# X15-Pi-Shield.net
KiCad netlist of a schematic drawn in EAGLE
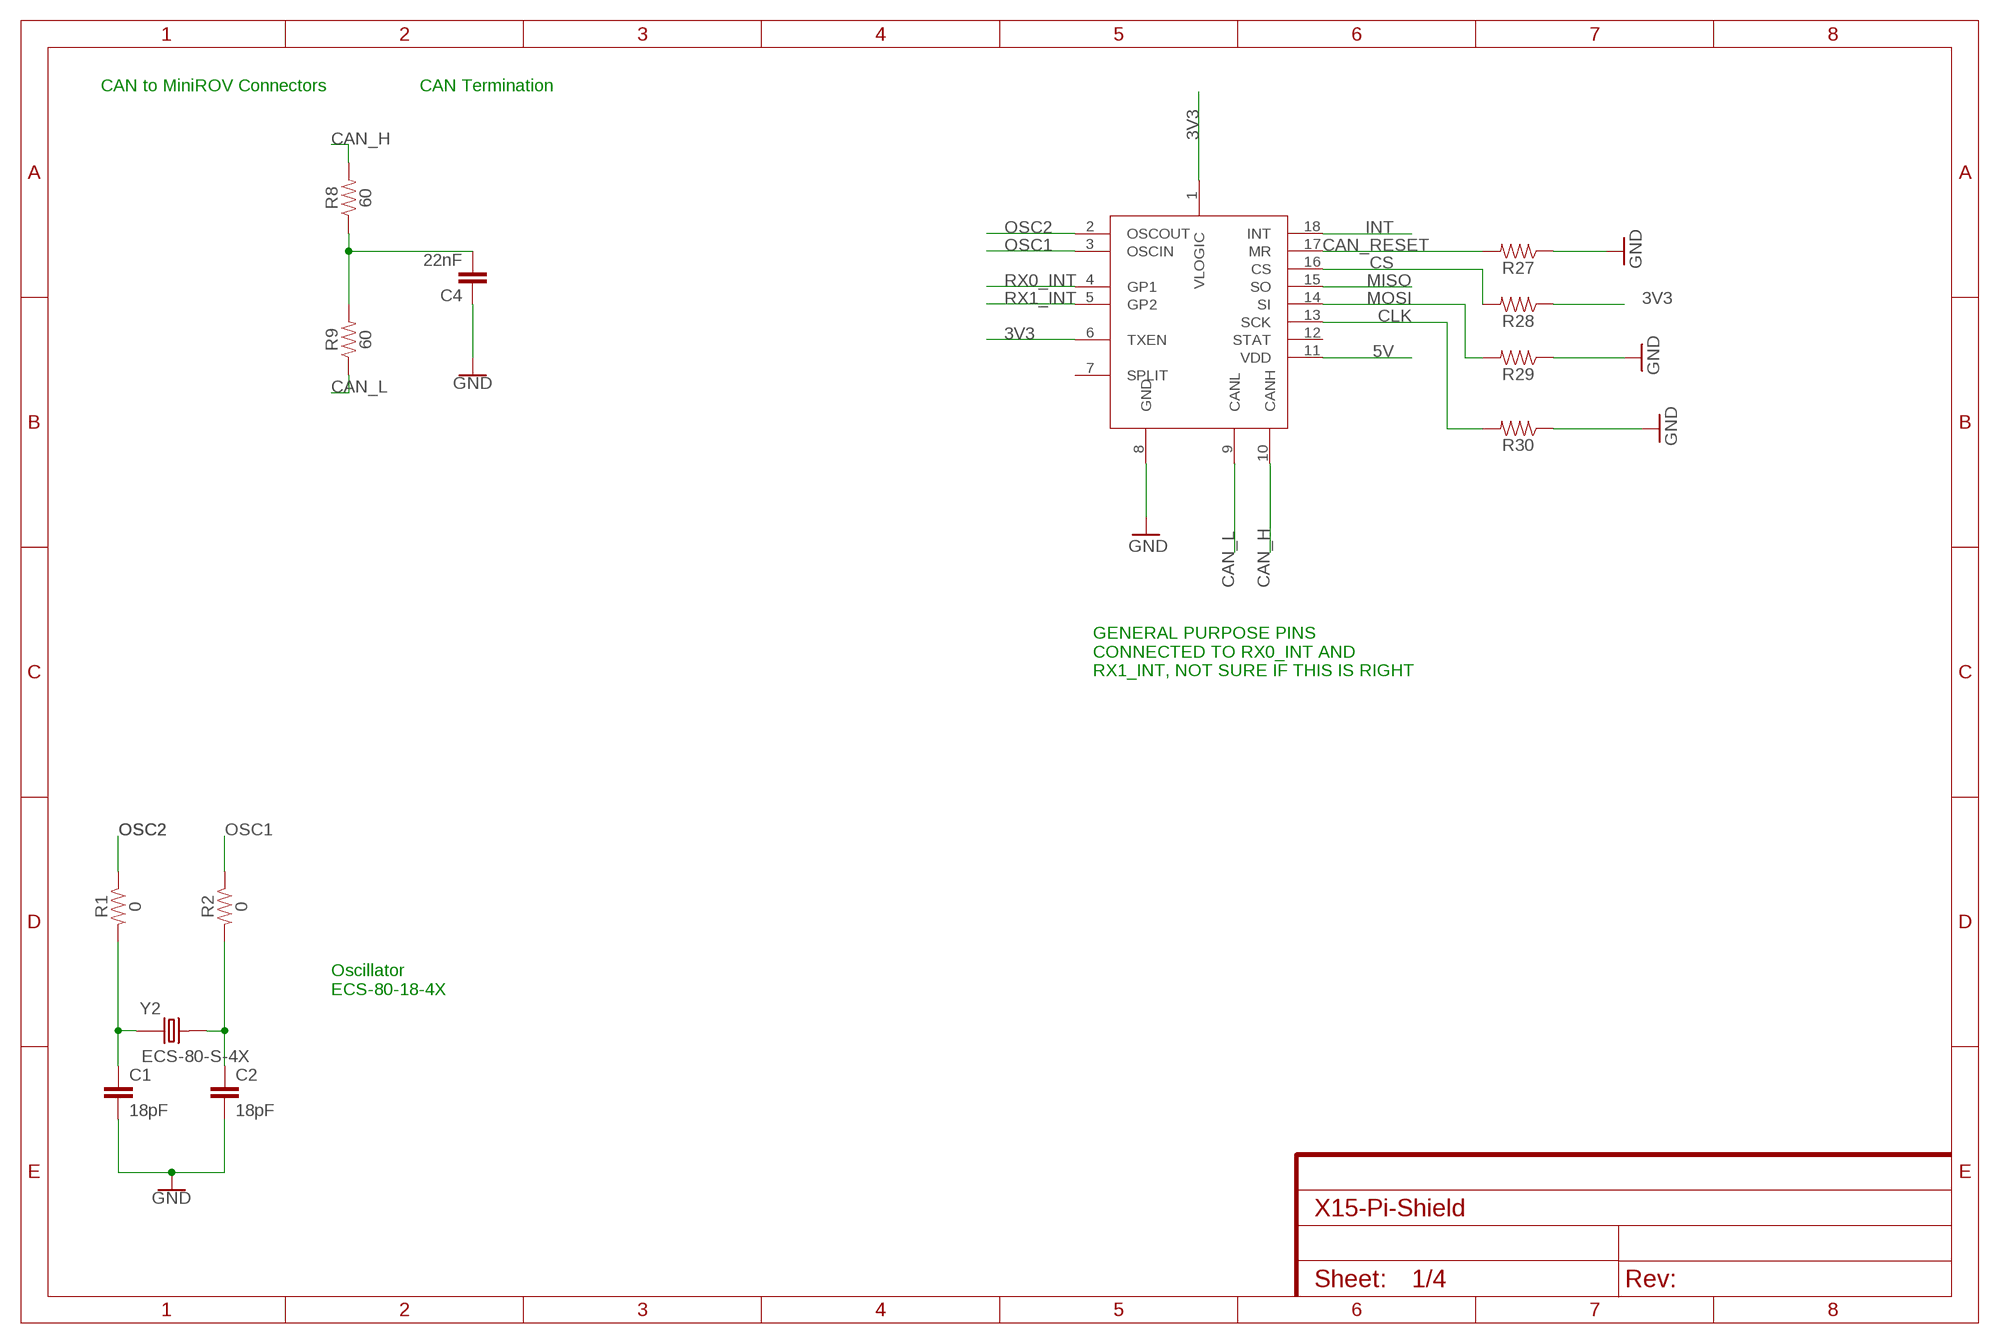
[diagram p0: schematic, sheet 1]
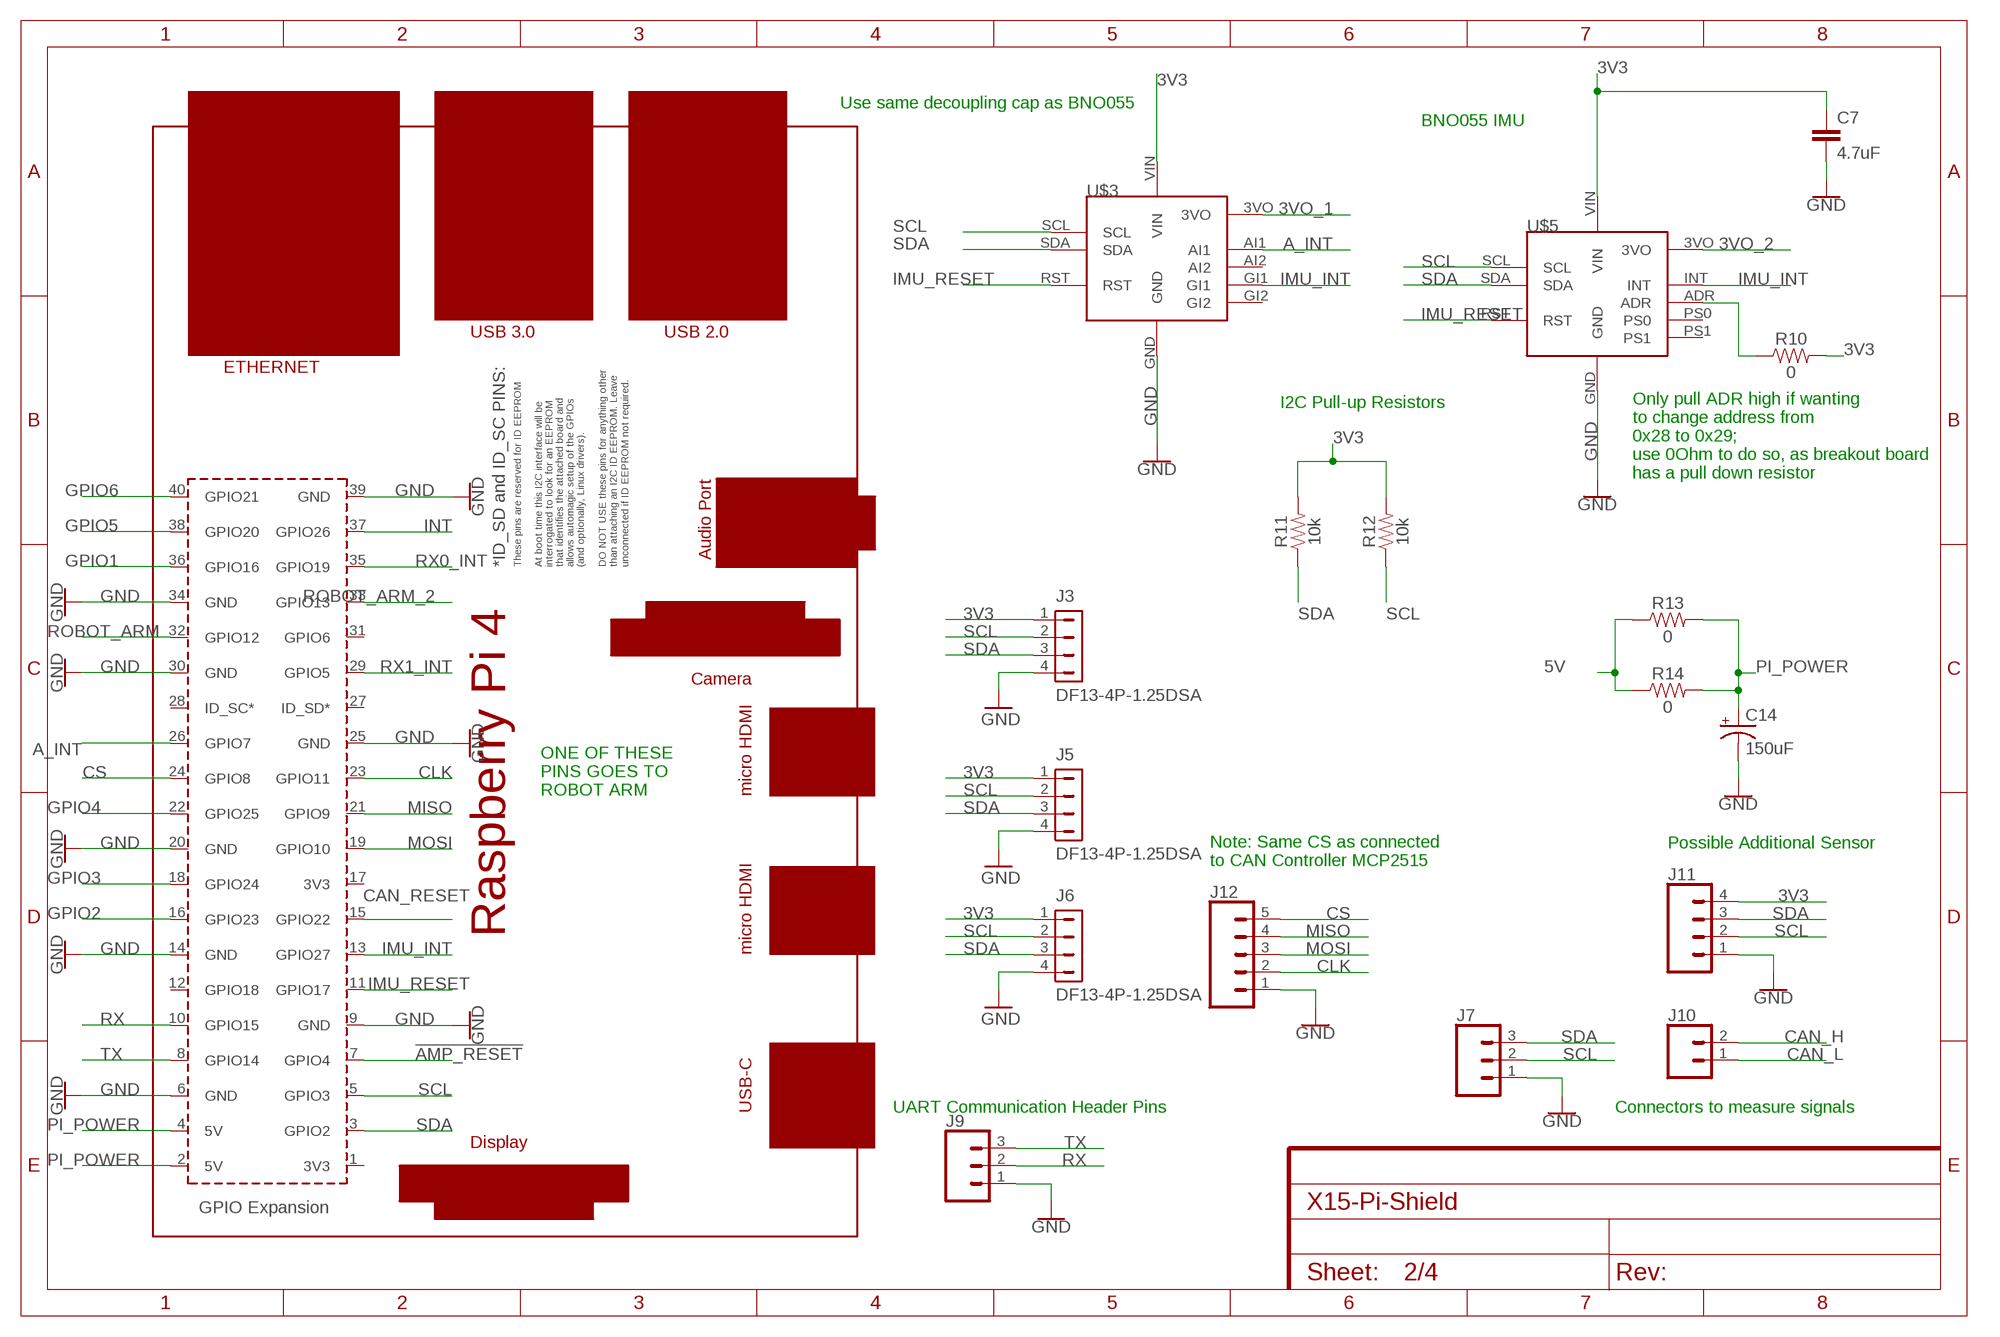
[diagram p1: schematic, sheet 2]
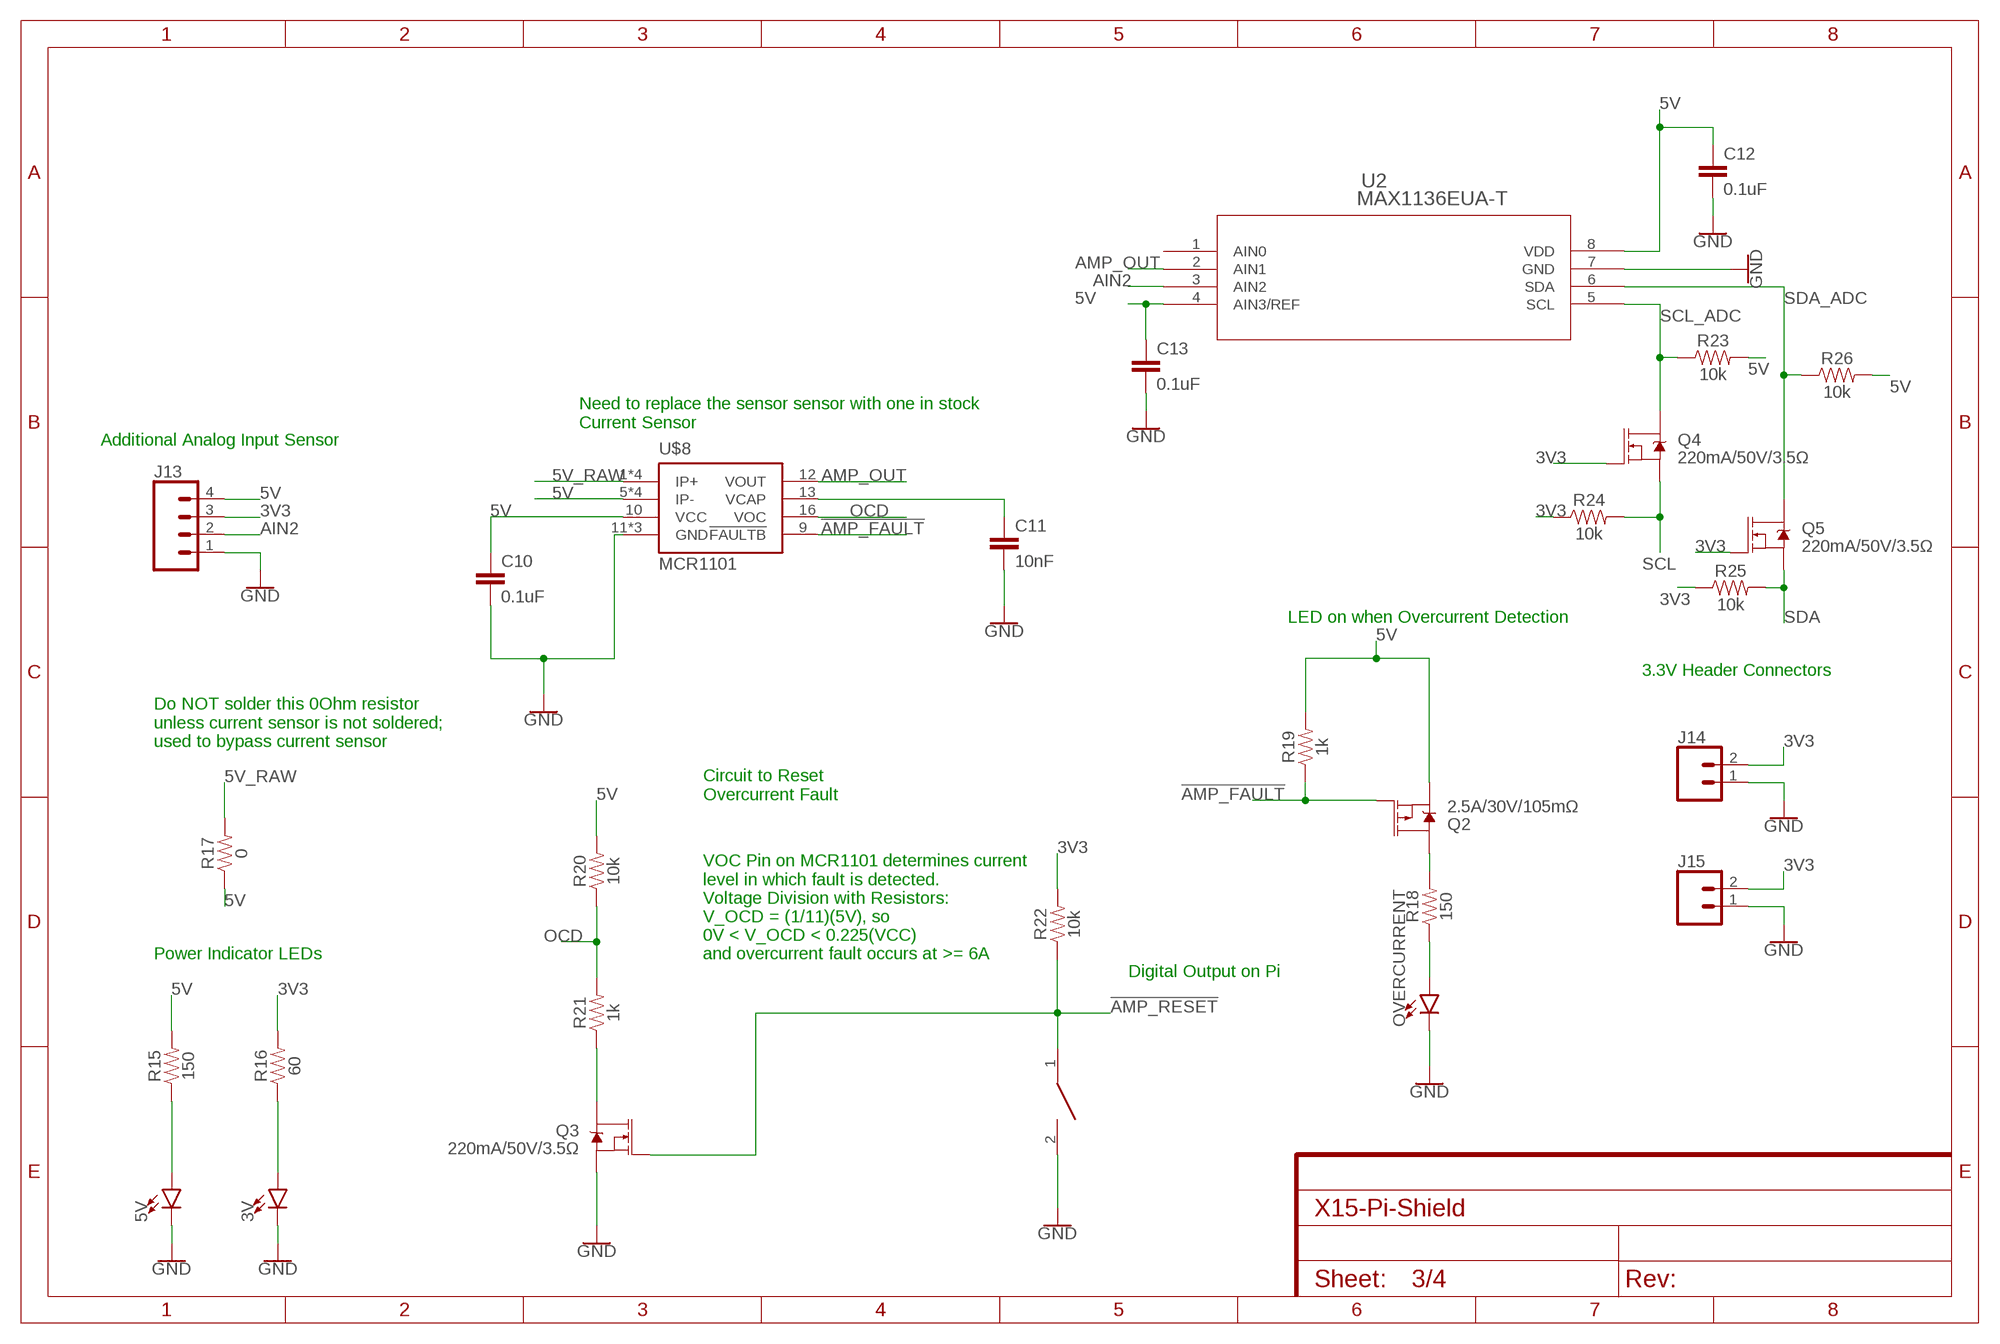
[diagram p2: schematic, sheet 3]
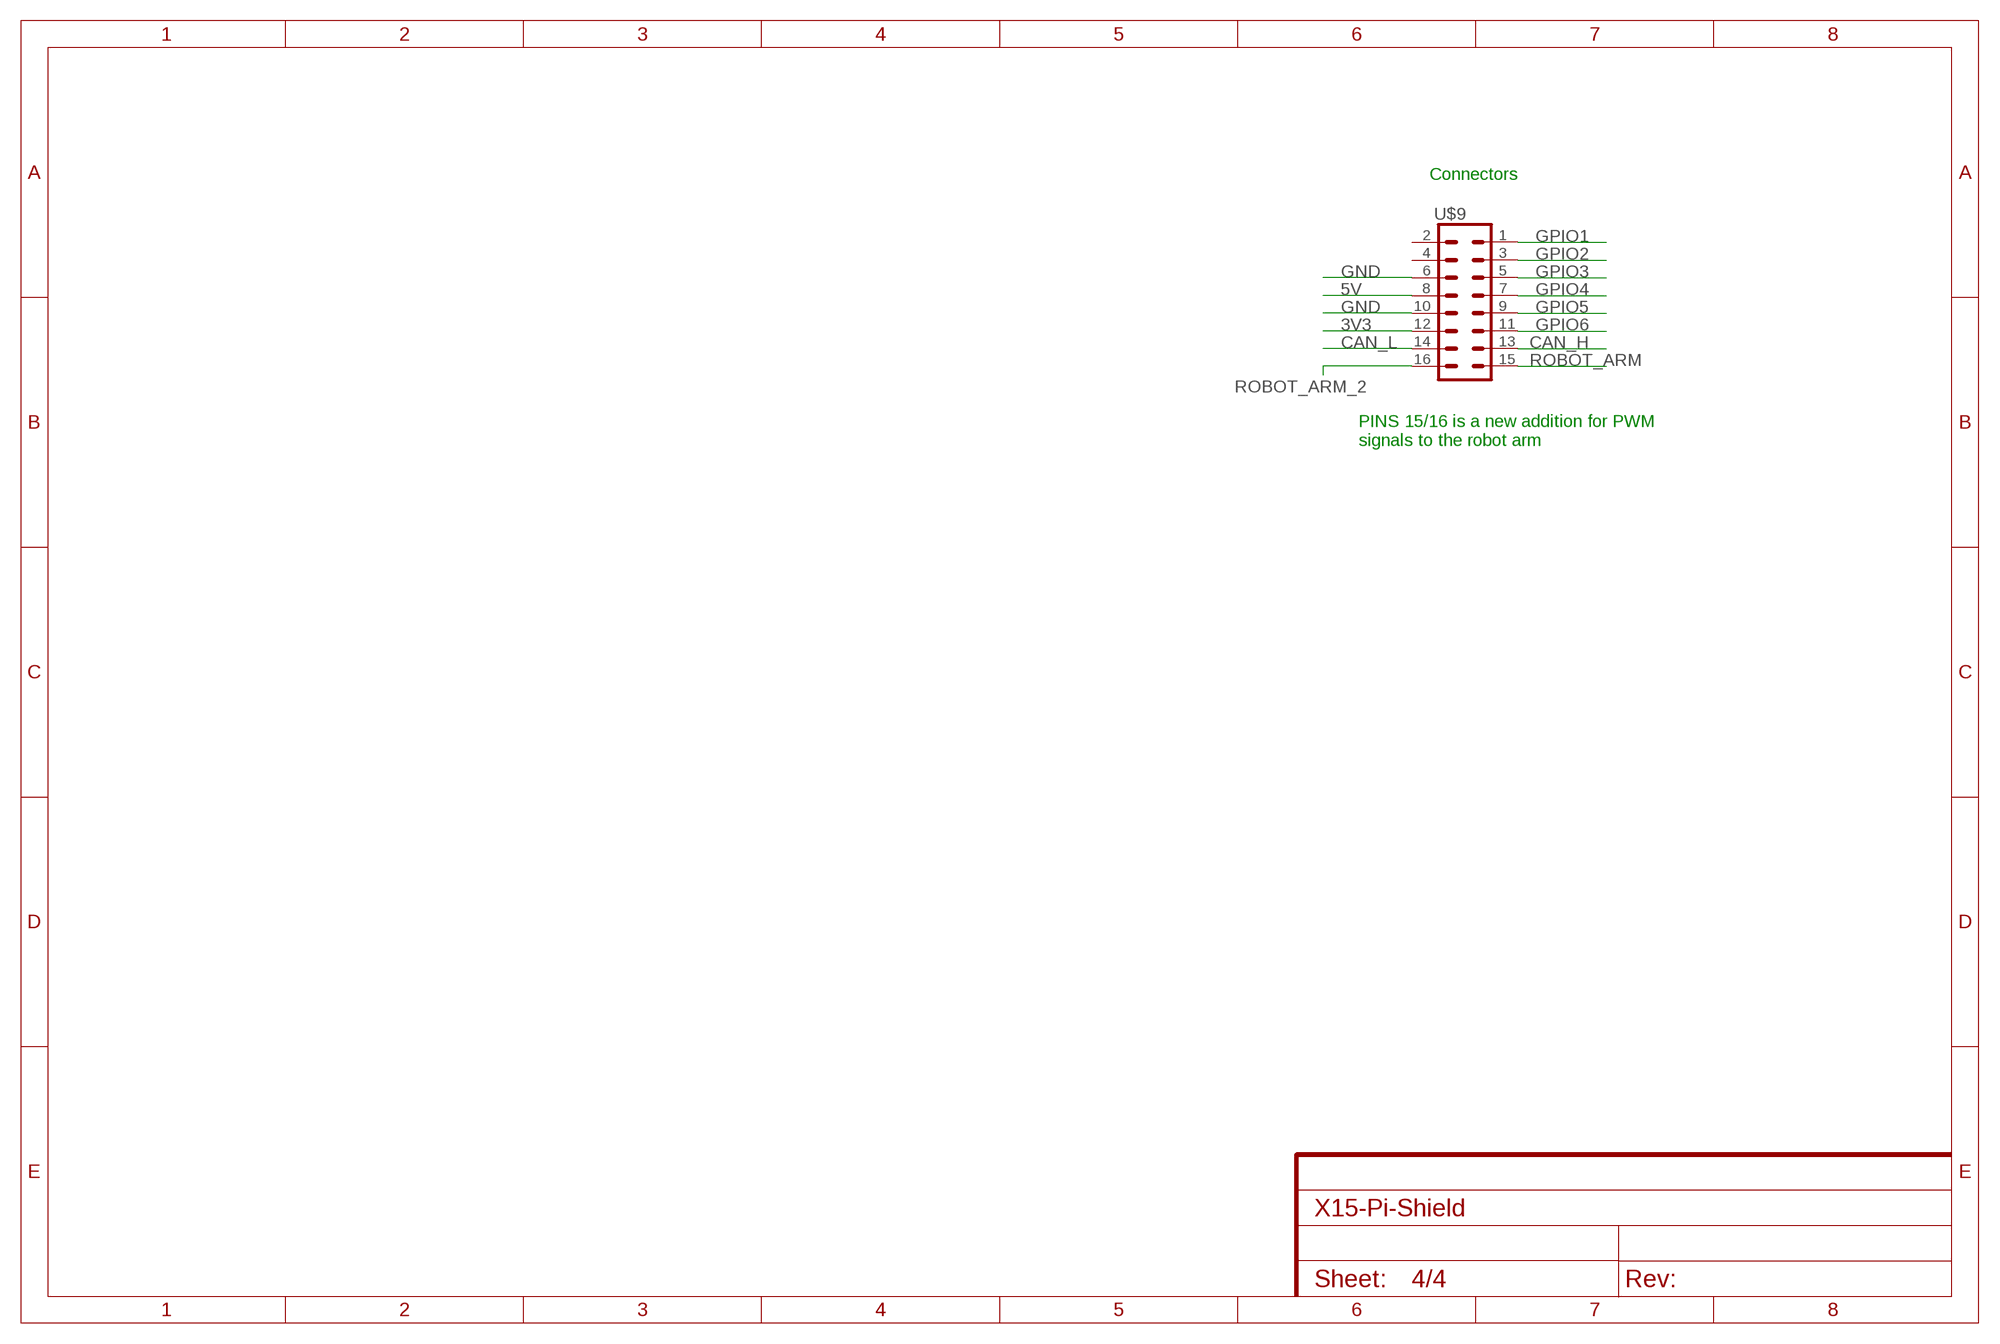
[diagram p3: schematic, sheet 4]

(export (version "E")
  (design (tool "Eeschema 10.0.6"))
  (components
    (comp (ref "3V")
      (value "LED0603")
      (footprint "eagle-import:LED-0603")
      (libsource (lib "eagle-import") (part "LED0603"))
    )
    (comp (ref "5V")
      (value "LED0603")
      (footprint "eagle-import:LED-0603")
      (libsource (lib "eagle-import") (part "LED0603"))
    )
    (comp (ref "C10")
      (value "0.1uF")
      (footprint "eagle-import:0603")
      (libsource (lib "eagle-import") (part "0.1UF-0603-25V-(+80/-20%)"))
    )
    (comp (ref "C11")
      (value "10nF")
      (footprint "eagle-import:0603")
      (libsource (lib "eagle-import") (part "10NF-0603-50V-10%"))
    )
    (comp (ref "C12")
      (value "0.1uF")
      (footprint "eagle-import:0603")
      (libsource (lib "eagle-import") (part "0.1UF-0603-25V-(+80/-20%)"))
    )
    (comp (ref "C13")
      (value "0.1uF")
      (footprint "eagle-import:0603")
      (libsource (lib "eagle-import") (part "0.1UF-0603-25V-(+80/-20%)"))
    )
    (comp (ref "J13")
      (value "CONN_04")
      (footprint "eagle-import:1X04")
      (libsource (lib "eagle-import") (part "CONN_04"))
    )
    (comp (ref "J14")
      (value "CONN_02")
      (footprint "eagle-import:1X02")
      (libsource (lib "eagle-import") (part "CONN_02"))
    )
    (comp (ref "J15")
      (value "CONN_02")
      (footprint "eagle-import:1X02")
      (libsource (lib "eagle-import") (part "CONN_02"))
    )
    (comp (ref "OVERCURRENT")
      (value "LED0603")
      (footprint "eagle-import:LED-0603")
      (libsource (lib "eagle-import") (part "LED0603"))
    )
    (comp (ref "Q2")
      (value "2.5A/30V/105mΩ")
      (footprint "eagle-import:SOT23-3")
      (libsource (lib "eagle-import") (part "MOSFET_PCH-DMG2307L"))
    )
    (comp (ref "Q3")
      (value "220mA/50V/3.5Ω")
      (footprint "eagle-import:SOT23-3")
      (libsource (lib "eagle-import") (part "MOSFET-NCH-BSS138"))
    )
    (comp (ref "Q4")
      (value "220mA/50V/3.5Ω")
      (footprint "eagle-import:SOT23-3")
      (libsource (lib "eagle-import") (part "MOSFET-NCH-BSS138"))
    )
    (comp (ref "Q5")
      (value "220mA/50V/3.5Ω")
      (footprint "eagle-import:SOT23-3")
      (libsource (lib "eagle-import") (part "MOSFET-NCH-BSS138"))
    )
    (comp (ref "R15")
      (value "150")
      (footprint "eagle-import:0603")
      (libsource (lib "eagle-import") (part "RESISTOR0603"))
    )
    (comp (ref "R16")
      (value "60")
      (footprint "eagle-import:0603")
      (libsource (lib "eagle-import") (part "RESISTOR0603"))
    )
    (comp (ref "R17")
      (value "0")
      (footprint "eagle-import:0603")
      (libsource (lib "eagle-import") (part "RESISTOR0603"))
    )
    (comp (ref "R18")
      (value "150")
      (footprint "eagle-import:0603")
      (libsource (lib "eagle-import") (part "RESISTOR0603"))
    )
    (comp (ref "R19")
      (value "1k")
      (footprint "eagle-import:0603")
      (libsource (lib "eagle-import") (part "RESISTOR0603"))
    )
    (comp (ref "R20")
      (value "10k")
      (footprint "eagle-import:0603")
      (libsource (lib "eagle-import") (part "RESISTOR0603"))
    )
    (comp (ref "R21")
      (value "1k")
      (footprint "eagle-import:0603")
      (libsource (lib "eagle-import") (part "RESISTOR0603"))
    )
    (comp (ref "R22")
      (value "10k")
      (footprint "eagle-import:0603")
      (libsource (lib "eagle-import") (part "RESISTOR0603"))
    )
    (comp (ref "R23")
      (value "10k")
      (footprint "eagle-import:0603")
      (libsource (lib "eagle-import") (part "RESISTOR0603"))
    )
    (comp (ref "R24")
      (value "10k")
      (footprint "eagle-import:0603")
      (libsource (lib "eagle-import") (part "RESISTOR0603"))
    )
    (comp (ref "R25")
      (value "10k")
      (footprint "eagle-import:0603")
      (libsource (lib "eagle-import") (part "RESISTOR0603"))
    )
    (comp (ref "R26")
      (value "10k")
      (footprint "eagle-import:0603")
      (libsource (lib "eagle-import") (part "RESISTOR0603"))
    )
    (comp (ref "U$7")
      (value "DISCRETECOMPONENTS_SWITCH")
      (footprint "eagle-import:DISCRETECOMPONENTS_SW_2512")
      (libsource (lib "eagle-import") (part "DISCRETECOMPONENTS_SWITCH"))
    )
    (comp (ref "U$8")
      (value "MCR1101")
      (footprint "eagle-import:SOIC-16")
      (libsource (lib "eagle-import") (part "MCR1101"))
    )
    (comp (ref "U2")
      (value "MAX1136EUA-T")
      (footprint "eagle-import:21-0036K")
      (fields
        (field (name "DIGI-KEY_PART_NUMBER") "MAX1136EUA+-ND")
        (field (name "MF") "Maxim Integrated")
        (field (name "MP") "MAX1136EUA+")
      )
      (libsource (lib "eagle-import") (part "MAX1136EUA-T"))
    )
    (comp (ref "U$9")
      (value "8X_CONN")
      (footprint "eagle-import:IPL7X2")
      (fields (field (name "SPICEPREFIX") "X"))
      (libsource (lib "eagle-import") (part "8X_CONN"))
    )
    (comp (ref "C1")
      (value "18pF")
      (footprint "eagle-import:0603")
      (libsource (lib "eagle-import") (part "18PF-0603-50V-5%"))
    )
    (comp (ref "C2")
      (value "18pF")
      (footprint "eagle-import:0603")
      (libsource (lib "eagle-import") (part "18PF-0603-50V-5%"))
    )
    (comp (ref "C4")
      (value "22nF")
      (footprint "eagle-import:0603")
      (libsource (lib "eagle-import") (part "22NF/22,000PF-0603-50V-10%"))
    )
    (comp (ref "R1")
      (value "0")
      (footprint "eagle-import:0603")
      (libsource (lib "eagle-import") (part "RESISTOR0603"))
    )
    (comp (ref "R2")
      (value "0")
      (footprint "eagle-import:0603")
      (libsource (lib "eagle-import") (part "RESISTOR0603"))
    )
    (comp (ref "R8")
      (value "60")
      (footprint "eagle-import:0603")
      (libsource (lib "eagle-import") (part "RESISTOR0603"))
    )
    (comp (ref "R9")
      (value "60")
      (footprint "eagle-import:0603")
      (libsource (lib "eagle-import") (part "RESISTOR0603"))
    )
    (comp (ref "R27")
      (value "50k")
      (footprint "eagle-import:0603")
      (libsource (lib "eagle-import") (part "RESISTOR0603"))
    )
    (comp (ref "R28")
      (value "50k")
      (footprint "eagle-import:0603")
      (libsource (lib "eagle-import") (part "RESISTOR0603"))
    )
    (comp (ref "R29")
      (value "50k")
      (footprint "eagle-import:0603")
      (libsource (lib "eagle-import") (part "RESISTOR0603"))
    )
    (comp (ref "R30")
      (value "50k")
      (footprint "eagle-import:0603")
      (libsource (lib "eagle-import") (part "RESISTOR0603"))
    )
    (comp (ref "U$6")
      (value "HI-3110")
      (footprint "eagle-import:SOIC-18")
      (libsource (lib "eagle-import") (part "HI-3110"))
    )
    (comp (ref "Y2")
      (value "ECS-80-S-4X")
      (footprint "eagle-import:XTAL_ECS-80-S-4X")
      (fields (field (name "DIGI-KEY_PART_NUMBER") "X1057-ND") (field (name "MF") "ECS International"))
      (libsource (lib "eagle-import") (part "ECS-80-S-4X"))
    )
    (comp (ref "C7")
      (value "4.7uF")
      (footprint "eagle-import:0603")
      (libsource (lib "eagle-import") (part "4.7UF0603"))
    )
    (comp (ref "C14")
      (value "150uF")
      (footprint "eagle-import:2917(7343-31-METRIC)")
      (libsource (lib "eagle-import") (part "C-TANTALUM(10UF_150UF)"))
    )
    (comp (ref "J3")
      (value "DF13-4P-1.25DSA")
      (footprint "eagle-import:DF13-4P-1.25DSA")
      (libsource (lib "eagle-import") (part "DF13-4P-1.25DSA"))
    )
    (comp (ref "J5")
      (value "DF13-4P-1.25DSA")
      (footprint "eagle-import:DF13-4P-1.25DSA")
      (libsource (lib "eagle-import") (part "DF13-4P-1.25DSA"))
    )
    (comp (ref "J6")
      (value "DF13-4P-1.25DSA")
      (footprint "eagle-import:DF13-4P-1.25DSA")
      (libsource (lib "eagle-import") (part "DF13-4P-1.25DSA"))
    )
    (comp (ref "J7")
      (value "CONN_03")
      (footprint "eagle-import:1X03")
      (libsource (lib "eagle-import") (part "CONN_03"))
    )
    (comp (ref "J9")
      (value "CONN_03")
      (footprint "eagle-import:1X03")
      (libsource (lib "eagle-import") (part "CONN_03"))
    )
    (comp (ref "J10")
      (value "CONN_02")
      (footprint "eagle-import:1X02")
      (libsource (lib "eagle-import") (part "CONN_02"))
    )
    (comp (ref "J11")
      (value "CONN_04")
      (footprint "eagle-import:1X04")
      (libsource (lib "eagle-import") (part "CONN_04"))
    )
    (comp (ref "J12")
      (value "CONN_05")
      (footprint "eagle-import:1X05")
      (libsource (lib "eagle-import") (part "CONN_05"))
    )
    (comp (ref "R10")
      (value "0")
      (footprint "eagle-import:0603")
      (libsource (lib "eagle-import") (part "RESISTOR0603"))
    )
    (comp (ref "R11")
      (value "10k")
      (footprint "eagle-import:0603")
      (libsource (lib "eagle-import") (part "RESISTOR0603"))
    )
    (comp (ref "R12")
      (value "10k")
      (footprint "eagle-import:0603")
      (libsource (lib "eagle-import") (part "RESISTOR0603"))
    )
    (comp (ref "R13")
      (value "0")
      (footprint "eagle-import:0603")
      (libsource (lib "eagle-import") (part "RESISTOR0603"))
    )
    (comp (ref "R14")
      (value "0")
      (footprint "eagle-import:0603")
      (libsource (lib "eagle-import") (part "RESISTOR0603"))
    )
    (comp (ref "U$3")
      (value "ADAFRUIT-FXOS8700-FXAS21002")
      (footprint "eagle-import:ADAFRUIT-FXOS8700-FXAS21002")
      (libsource (lib "eagle-import") (part "ADAFRUIT-FXOS8700-FXAS21002"))
    )
    (comp (ref "U$4")
      (value "RPI4")
      (footprint "eagle-import:RPI4")
      (libsource (lib "eagle-import") (part "RPI4"))
    )
    (comp (ref "U$5")
      (value "ADAFRUIT-BNO055")
      (footprint "eagle-import:ADAFRUIT-BNO055")
      (libsource (lib "eagle-import") (part "ADAFRUIT-BNO055"))
    )
  )
  (nets
    (net (code "1") (name "3V3") (class "Default")
      (node (ref "C7") (pin "1") (pinfunction "1_1") (pintype "passive"))
      (node (ref "J11") (pin "4") (pinfunction "4_4") (pintype "passive"))
      (node (ref "J13") (pin "3") (pinfunction "3_3") (pintype "passive"))
      (node (ref "J14") (pin "2") (pinfunction "2_2") (pintype "passive"))
      (node (ref "J15") (pin "2") (pinfunction "2_2") (pintype "passive"))
      (node (ref "J3") (pin "1") (pinfunction "1_1") (pintype "passive"))
      (node (ref "J5") (pin "1") (pinfunction "1_1") (pintype "passive"))
      (node (ref "J6") (pin "1") (pinfunction "1_1") (pintype "passive"))
      (node (ref "Q4") (pin "1") (pinfunction "G_1") (pintype "bidirectional"))
      (node (ref "Q5") (pin "1") (pinfunction "G_1") (pintype "bidirectional"))
      (node (ref "R10") (pin "2") (pinfunction "2_2") (pintype "passive"))
      (node (ref "R11") (pin "2") (pinfunction "2_2") (pintype "passive"))
      (node (ref "R12") (pin "2") (pinfunction "2_2") (pintype "passive"))
      (node (ref "R16") (pin "2") (pinfunction "2_2") (pintype "passive"))
      (node (ref "R22") (pin "2") (pinfunction "2_2") (pintype "passive"))
      (node (ref "R24") (pin "1") (pinfunction "1_1") (pintype "passive"))
      (node (ref "R25") (pin "1") (pinfunction "1_1") (pintype "passive"))
      (node (ref "R28") (pin "1") (pinfunction "1_1") (pintype "passive"))
      (node (ref "U$3") (pin "VIN") (pinfunction "VIN_VIN") (pintype "power_in"))
      (node (ref "U$5") (pin "VIN") (pinfunction "VIN_VIN") (pintype "power_in"))
      (node (ref "U$6") (pin "1") (pinfunction "VLOGIC_1") (pintype "bidirectional"))
      (node (ref "U$6") (pin "6") (pinfunction "TXEN_6") (pintype "bidirectional"))
      (node (ref "U$9") (pin "12") (pinfunction "23_12") (pintype "passive"))
    )
    (net (code "2") (name "3VO_1") (class "Default")
      (node (ref "U$3") (pin "3VO") (pinfunction "3VO_3VO") (pintype "power_in"))
    )
    (net (code "3") (name "3VO_2") (class "Default")
      (node (ref "U$5") (pin "3VO") (pinfunction "3VO_3VO") (pintype "power_in"))
    )
    (net (code "4") (name "5V") (class "Default")
      (node (ref "C10") (pin "1") (pinfunction "1_1") (pintype "passive"))
      (node (ref "C12") (pin "1") (pinfunction "1_1") (pintype "passive"))
      (node (ref "C13") (pin "1") (pinfunction "1_1") (pintype "passive"))
      (node (ref "J13") (pin "4") (pinfunction "4_4") (pintype "passive"))
      (node (ref "Q2") (pin "2") (pinfunction "S_2") (pintype "bidirectional"))
      (node (ref "R13") (pin "1") (pinfunction "1_1") (pintype "passive"))
      (node (ref "R14") (pin "1") (pinfunction "1_1") (pintype "passive"))
      (node (ref "R15") (pin "2") (pinfunction "2_2") (pintype "passive"))
      (node (ref "R17") (pin "1") (pinfunction "1_1") (pintype "passive"))
      (node (ref "R19") (pin "2") (pinfunction "2_2") (pintype "passive"))
      (node (ref "R20") (pin "2") (pinfunction "2_2") (pintype "passive"))
      (node (ref "R23") (pin "2") (pinfunction "2_2") (pintype "passive"))
      (node (ref "R26") (pin "2") (pinfunction "2_2") (pintype "passive"))
      (node (ref "U$6") (pin "11") (pinfunction "VDD_11") (pintype "bidirectional"))
      (node (ref "U$8") (pin "10") (pinfunction "VCC_10") (pintype "bidirectional"))
      (node (ref "U$8") (pin "5") (pinfunction "IP-_5") (pintype "bidirectional"))
      (node (ref "U$8") (pin "6") (pinfunction "IP-_6") (pintype "bidirectional"))
      (node (ref "U$8") (pin "7") (pinfunction "IP-_7") (pintype "bidirectional"))
      (node (ref "U$8") (pin "8") (pinfunction "IP-_8") (pintype "bidirectional"))
      (node (ref "U$9") (pin "8") (pinfunction "19_8") (pintype "passive"))
      (node (ref "U2") (pin "4") (pinfunction "AIN3/REF_4") (pintype "bidirectional"))
      (node (ref "U2") (pin "8") (pinfunction "VDD_8") (pintype "power_in"))
    )
    (net (code "5") (name "5V_RAW") (class "Default")
      (node (ref "R17") (pin "2") (pinfunction "2_2") (pintype "passive"))
      (node (ref "U$8") (pin "1") (pinfunction "IP+_1") (pintype "bidirectional"))
      (node (ref "U$8") (pin "2") (pinfunction "IP+_2") (pintype "bidirectional"))
      (node (ref "U$8") (pin "3") (pinfunction "IP+_3") (pintype "bidirectional"))
      (node (ref "U$8") (pin "4") (pinfunction "IP+_4") (pintype "bidirectional"))
    )
    (net (code "6") (name "AIN2") (class "Default")
      (node (ref "J13") (pin "2") (pinfunction "2_2") (pintype "passive"))
      (node (ref "U2") (pin "3") (pinfunction "AIN2_3") (pintype "bidirectional"))
    )
    (net (code "7") (name "AMP_OUT") (class "Default")
      (node (ref "U$8") (pin "12") (pinfunction "VOUT_12") (pintype "bidirectional"))
      (node (ref "U2") (pin "2") (pinfunction "AIN1_2") (pintype "bidirectional"))
    )
    (net (code "8") (name "A_INT") (class "Default")
      (node (ref "U$3") (pin "AI1") (pinfunction "AI1_AI1") (pintype "output"))
      (node (ref "U$4") (pin "26") (pinfunction "GPIO7_26") (pintype "bidirectional"))
    )
    (net (code "9") (name "CAN_H") (class "Default")
      (node (ref "J10") (pin "2") (pinfunction "2_2") (pintype "passive"))
      (node (ref "R8") (pin "2") (pinfunction "2_2") (pintype "passive"))
      (node (ref "U$6") (pin "10") (pinfunction "CANH_10") (pintype "bidirectional"))
      (node (ref "U$9") (pin "13") (pinfunction "1_13") (pintype "passive"))
    )
    (net (code "10") (name "CAN_L") (class "Default")
      (node (ref "J10") (pin "1") (pinfunction "1_1") (pintype "passive"))
      (node (ref "R9") (pin "1") (pinfunction "1_1") (pintype "passive"))
      (node (ref "U$6") (pin "9") (pinfunction "CANL_9") (pintype "bidirectional"))
      (node (ref "U$9") (pin "14") (pinfunction "2_14") (pintype "passive"))
    )
    (net (code "11") (name "CAN_RESET") (class "Default")
      (node (ref "R27") (pin "2") (pinfunction "2_2") (pintype "passive"))
      (node (ref "U$4") (pin "15") (pinfunction "GPIO22_15") (pintype "bidirectional"))
      (node (ref "U$6") (pin "17") (pinfunction "MR_17") (pintype "bidirectional"))
    )
    (net (code "12") (name "CLK") (class "Default")
      (node (ref "J12") (pin "2") (pinfunction "2_2") (pintype "passive"))
      (node (ref "R30") (pin "2") (pinfunction "2_2") (pintype "passive"))
      (node (ref "U$4") (pin "23") (pinfunction "GPIO11_23") (pintype "bidirectional"))
      (node (ref "U$6") (pin "13") (pinfunction "SCK_13") (pintype "bidirectional"))
    )
    (net (code "13") (name "CS") (class "Default")
      (node (ref "J12") (pin "5") (pinfunction "5_5") (pintype "passive"))
      (node (ref "R28") (pin "2") (pinfunction "2_2") (pintype "passive"))
      (node (ref "U$4") (pin "24") (pinfunction "GPIO8_24") (pintype "bidirectional"))
      (node (ref "U$6") (pin "16") (pinfunction "CS_16") (pintype "bidirectional"))
    )
    (net (code "14") (name "GND") (class "Default")
      (node (ref "3V") (pin "C") (pinfunction "C_C") (pintype "passive"))
      (node (ref "5V") (pin "C") (pinfunction "C_C") (pintype "passive"))
      (node (ref "C1") (pin "2") (pinfunction "2_2") (pintype "passive"))
      (node (ref "C10") (pin "2") (pinfunction "2_2") (pintype "passive"))
      (node (ref "C11") (pin "2") (pinfunction "2_2") (pintype "passive"))
      (node (ref "C12") (pin "2") (pinfunction "2_2") (pintype "passive"))
      (node (ref "C13") (pin "2") (pinfunction "2_2") (pintype "passive"))
      (node (ref "C14") (pin "-") (pinfunction "-_-") (pintype "passive"))
      (node (ref "C2") (pin "2") (pinfunction "2_2") (pintype "passive"))
      (node (ref "C4") (pin "1") (pinfunction "1_1") (pintype "passive"))
      (node (ref "C7") (pin "2") (pinfunction "2_2") (pintype "passive"))
      (node (ref "J11") (pin "1") (pinfunction "1_1") (pintype "passive"))
      (node (ref "J12") (pin "1") (pinfunction "1_1") (pintype "passive"))
      (node (ref "J13") (pin "1") (pinfunction "1_1") (pintype "passive"))
      (node (ref "J14") (pin "1") (pinfunction "1_1") (pintype "passive"))
      (node (ref "J15") (pin "1") (pinfunction "1_1") (pintype "passive"))
      (node (ref "J3") (pin "4") (pinfunction "4_4") (pintype "passive"))
      (node (ref "J5") (pin "4") (pinfunction "4_4") (pintype "passive"))
      (node (ref "J6") (pin "4") (pinfunction "4_4") (pintype "passive"))
      (node (ref "J7") (pin "1") (pinfunction "1_1") (pintype "passive"))
      (node (ref "J9") (pin "1") (pinfunction "1_1") (pintype "passive"))
      (node (ref "OVERCURRENT") (pin "C") (pinfunction "C_C") (pintype "passive"))
      (node (ref "Q3") (pin "2") (pinfunction "S_2") (pintype "bidirectional"))
      (node (ref "R27") (pin "1") (pinfunction "1_1") (pintype "passive"))
      (node (ref "R29") (pin "1") (pinfunction "1_1") (pintype "passive"))
      (node (ref "R30") (pin "1") (pinfunction "1_1") (pintype "passive"))
      (node (ref "U$3") (pin "GND") (pinfunction "GND_GND") (pintype "power_in"))
      (node (ref "U$4") (pin "14") (pinfunction "GND_14") (pintype "bidirectional"))
      (node (ref "U$4") (pin "20") (pinfunction "GND_20") (pintype "bidirectional"))
      (node (ref "U$4") (pin "25") (pinfunction "GND_25") (pintype "bidirectional"))
      (node (ref "U$4") (pin "30") (pinfunction "GND_30") (pintype "bidirectional"))
      (node (ref "U$4") (pin "34") (pinfunction "GND_34") (pintype "bidirectional"))
      (node (ref "U$4") (pin "39") (pinfunction "GND_39") (pintype "bidirectional"))
      (node (ref "U$4") (pin "6") (pinfunction "GND_6") (pintype "bidirectional"))
      (node (ref "U$4") (pin "9") (pinfunction "GND_9") (pintype "bidirectional"))
      (node (ref "U$5") (pin "GND") (pinfunction "GND_GND") (pintype "power_in"))
      (node (ref "U$6") (pin "8") (pinfunction "GND_8") (pintype "bidirectional"))
      (node (ref "U$7") (pin "2") (pinfunction "P$2_2") (pintype "bidirectional"))
      (node (ref "U$8") (pin "11") (pinfunction "GND_11") (pintype "bidirectional"))
      (node (ref "U$8") (pin "14") (pinfunction "GND_14") (pintype "bidirectional"))
      (node (ref "U$8") (pin "15") (pinfunction "GND_15") (pintype "bidirectional"))
      (node (ref "U$9") (pin "10") (pinfunction "21_10") (pintype "passive"))
      (node (ref "U$9") (pin "6") (pinfunction "17_6") (pintype "passive"))
      (node (ref "U2") (pin "7") (pinfunction "GND_7") (pintype "power_in"))
    )
    (net (code "15") (name "GPIO1") (class "Default")
      (node (ref "U$4") (pin "36") (pinfunction "GPIO16_36") (pintype "bidirectional"))
      (node (ref "U$9") (pin "1") (pinfunction "14_1") (pintype "passive"))
    )
    (net (code "16") (name "GPIO2") (class "Default")
      (node (ref "U$4") (pin "16") (pinfunction "GPIO23_16") (pintype "bidirectional"))
      (node (ref "U$9") (pin "3") (pinfunction "16_3") (pintype "passive"))
    )
    (net (code "17") (name "GPIO3") (class "Default")
      (node (ref "U$4") (pin "18") (pinfunction "GPIO24_18") (pintype "bidirectional"))
      (node (ref "U$9") (pin "5") (pinfunction "18_5") (pintype "passive"))
    )
    (net (code "18") (name "GPIO4") (class "Default")
      (node (ref "U$4") (pin "22") (pinfunction "GPIO25_22") (pintype "bidirectional"))
      (node (ref "U$9") (pin "7") (pinfunction "20_7") (pintype "passive"))
    )
    (net (code "19") (name "GPIO5") (class "Default")
      (node (ref "U$4") (pin "38") (pinfunction "GPIO20_38") (pintype "bidirectional"))
      (node (ref "U$9") (pin "9") (pinfunction "22_9") (pintype "passive"))
    )
    (net (code "20") (name "GPIO6") (class "Default")
      (node (ref "U$4") (pin "40") (pinfunction "GPIO21_40") (pintype "bidirectional"))
      (node (ref "U$9") (pin "11") (pinfunction "24_11") (pintype "passive"))
    )
    (net (code "21") (name "IMU_INT") (class "Default")
      (node (ref "U$3") (pin "GI1") (pinfunction "GI1_GI1") (pintype "output"))
      (node (ref "U$4") (pin "13") (pinfunction "GPIO27_13") (pintype "bidirectional"))
      (node (ref "U$5") (pin "INT") (pinfunction "INT_INT") (pintype "output"))
    )
    (net (code "22") (name "IMU_RESET") (class "Default")
      (node (ref "U$3") (pin "RST") (pinfunction "RST_RST") (pintype "input"))
      (node (ref "U$4") (pin "11") (pinfunction "GPIO17_11") (pintype "bidirectional"))
      (node (ref "U$5") (pin "RST") (pinfunction "RST_RST") (pintype "input"))
    )
    (net (code "23") (name "INT") (class "Default")
      (node (ref "U$4") (pin "37") (pinfunction "GPIO26_37") (pintype "bidirectional"))
      (node (ref "U$6") (pin "18") (pinfunction "INT_18") (pintype "bidirectional"))
    )
    (net (code "24") (name "MISO") (class "Default")
      (node (ref "J12") (pin "4") (pinfunction "4_4") (pintype "passive"))
      (node (ref "U$4") (pin "21") (pinfunction "GPIO9_21") (pintype "bidirectional"))
      (node (ref "U$6") (pin "15") (pinfunction "SO_15") (pintype "bidirectional"))
    )
    (net (code "25") (name "MOSI") (class "Default")
      (node (ref "J12") (pin "3") (pinfunction "3_3") (pintype "passive"))
      (node (ref "R29") (pin "2") (pinfunction "2_2") (pintype "passive"))
      (node (ref "U$4") (pin "19") (pinfunction "GPIO10_19") (pintype "bidirectional"))
      (node (ref "U$6") (pin "14") (pinfunction "SI_14") (pintype "bidirectional"))
    )
    (net (code "26") (name "Net-(3V-PadA)") (class "Default")
      (node (ref "3V") (pin "A") (pinfunction "A_A") (pintype "passive"))
      (node (ref "R16") (pin "1") (pinfunction "1_1") (pintype "passive"))
    )
    (net (code "27") (name "Net-(5V-PadA)") (class "Default")
      (node (ref "5V") (pin "A") (pinfunction "A_A") (pintype "passive"))
      (node (ref "R15") (pin "1") (pinfunction "1_1") (pintype "passive"))
    )
    (net (code "28") (name "Net-(C1-Pad1)") (class "Default")
      (node (ref "C1") (pin "1") (pinfunction "1_1") (pintype "passive"))
      (node (ref "R1") (pin "2") (pinfunction "2_2") (pintype "passive"))
      (node (ref "Y2") (pin "1") (pinfunction "1_1") (pintype "passive"))
    )
    (net (code "29") (name "Net-(C2-Pad1)") (class "Default")
      (node (ref "C2") (pin "1") (pinfunction "1_1") (pintype "passive"))
      (node (ref "R2") (pin "2") (pinfunction "2_2") (pintype "passive"))
      (node (ref "Y2") (pin "2") (pinfunction "2_2") (pintype "passive"))
    )
    (net (code "30") (name "Net-(C4-Pad2)") (class "Default")
      (node (ref "C4") (pin "2") (pinfunction "2_2") (pintype "passive"))
      (node (ref "R8") (pin "1") (pinfunction "1_1") (pintype "passive"))
      (node (ref "R9") (pin "2") (pinfunction "2_2") (pintype "passive"))
    )
    (net (code "31") (name "Net-(OVERCURRENT-PadA)") (class "Default")
      (node (ref "OVERCURRENT") (pin "A") (pinfunction "A_A") (pintype "passive"))
      (node (ref "R18") (pin "1") (pinfunction "1_1") (pintype "passive"))
    )
    (net (code "32") (name "Net-(Q2-D)") (class "Default")
      (node (ref "Q2") (pin "3") (pinfunction "D_3") (pintype "bidirectional"))
      (node (ref "R18") (pin "2") (pinfunction "2_2") (pintype "passive"))
    )
    (net (code "33") (name "Net-(Q3-D)") (class "Default")
      (node (ref "Q3") (pin "3") (pinfunction "D_3") (pintype "bidirectional"))
      (node (ref "R21") (pin "1") (pinfunction "1_1") (pintype "passive"))
    )
    (net (code "34") (name "Net-(R10-Pad1)") (class "Default")
      (node (ref "R10") (pin "1") (pinfunction "1_1") (pintype "passive"))
      (node (ref "U$5") (pin "ADR") (pinfunction "ADR_ADR") (pintype "input"))
    )
    (net (code "35") (name "Net-(U$8-VCAP)") (class "Default")
      (node (ref "C11") (pin "1") (pinfunction "1_1") (pintype "passive"))
      (node (ref "U$8") (pin "13") (pinfunction "VCAP_13") (pintype "bidirectional"))
    )
    (net (code "36") (name "OCD") (class "Default")
      (node (ref "R20") (pin "1") (pinfunction "1_1") (pintype "passive"))
      (node (ref "R21") (pin "2") (pinfunction "2_2") (pintype "passive"))
      (node (ref "U$8") (pin "16") (pinfunction "VOC_16") (pintype "bidirectional"))
    )
    (net (code "37") (name "OSC1") (class "Default")
      (node (ref "R2") (pin "1") (pinfunction "1_1") (pintype "passive"))
      (node (ref "U$6") (pin "3") (pinfunction "OSCIN_3") (pintype "bidirectional"))
    )
    (net (code "38") (name "OSC2") (class "Default")
      (node (ref "R1") (pin "1") (pinfunction "1_1") (pintype "passive"))
      (node (ref "U$6") (pin "2") (pinfunction "OSCOUT_2") (pintype "bidirectional"))
    )
    (net (code "39") (name "PI_POWER") (class "Default")
      (node (ref "C14") (pin "+") (pinfunction "+_+") (pintype "passive"))
      (node (ref "R13") (pin "2") (pinfunction "2_2") (pintype "passive"))
      (node (ref "R14") (pin "2") (pinfunction "2_2") (pintype "passive"))
      (node (ref "U$4") (pin "2") (pinfunction "5V_2") (pintype "bidirectional"))
      (node (ref "U$4") (pin "4") (pinfunction "5V_4") (pintype "bidirectional"))
    )
    (net (code "40") (name "ROBOT_ARM") (class "Default")
      (node (ref "U$4") (pin "32") (pinfunction "GPIO12_32") (pintype "bidirectional"))
      (node (ref "U$9") (pin "15") (pinfunction "4_15") (pintype "passive"))
    )
    (net (code "41") (name "ROBOT_ARM_2") (class "Default")
      (node (ref "U$4") (pin "33") (pinfunction "GPIO13_33") (pintype "bidirectional"))
      (node (ref "U$9") (pin "16") (pinfunction "3_16") (pintype "passive"))
    )
    (net (code "42") (name "RX") (class "Default")
      (node (ref "J9") (pin "2") (pinfunction "2_2") (pintype "passive"))
      (node (ref "U$4") (pin "10") (pinfunction "GPIO15_10") (pintype "bidirectional"))
    )
    (net (code "43") (name "RX0_INT") (class "Default")
      (node (ref "U$4") (pin "35") (pinfunction "GPIO19_35") (pintype "bidirectional"))
      (node (ref "U$6") (pin "4") (pinfunction "GP1_4") (pintype "bidirectional"))
    )
    (net (code "44") (name "RX1_INT") (class "Default")
      (node (ref "U$4") (pin "29") (pinfunction "GPIO5_29") (pintype "bidirectional"))
      (node (ref "U$6") (pin "5") (pinfunction "GP2_5") (pintype "bidirectional"))
    )
    (net (code "45") (name "SCL") (class "Default")
      (node (ref "J11") (pin "2") (pinfunction "2_2") (pintype "passive"))
      (node (ref "J3") (pin "2") (pinfunction "2_2") (pintype "passive"))
      (node (ref "J5") (pin "2") (pinfunction "2_2") (pintype "passive"))
      (node (ref "J6") (pin "2") (pinfunction "2_2") (pintype "passive"))
      (node (ref "J7") (pin "2") (pinfunction "2_2") (pintype "passive"))
      (node (ref "Q4") (pin "2") (pinfunction "S_2") (pintype "bidirectional"))
      (node (ref "R12") (pin "1") (pinfunction "1_1") (pintype "passive"))
      (node (ref "R24") (pin "2") (pinfunction "2_2") (pintype "passive"))
      (node (ref "U$3") (pin "SCL") (pinfunction "SCL_SCL") (pintype "bidirectional"))
      (node (ref "U$4") (pin "5") (pinfunction "GPIO3_5") (pintype "bidirectional"))
      (node (ref "U$5") (pin "SCL") (pinfunction "SCL_SCL") (pintype "bidirectional"))
    )
    (net (code "46") (name "SCL_ADC") (class "Default")
      (node (ref "Q4") (pin "3") (pinfunction "D_3") (pintype "bidirectional"))
      (node (ref "R23") (pin "1") (pinfunction "1_1") (pintype "passive"))
      (node (ref "U2") (pin "5") (pinfunction "SCL_5") (pintype "bidirectional"))
    )
    (net (code "47") (name "SDA") (class "Default")
      (node (ref "J11") (pin "3") (pinfunction "3_3") (pintype "passive"))
      (node (ref "J3") (pin "3") (pinfunction "3_3") (pintype "passive"))
      (node (ref "J5") (pin "3") (pinfunction "3_3") (pintype "passive"))
      (node (ref "J6") (pin "3") (pinfunction "3_3") (pintype "passive"))
      (node (ref "J7") (pin "3") (pinfunction "3_3") (pintype "passive"))
      (node (ref "Q5") (pin "2") (pinfunction "S_2") (pintype "bidirectional"))
      (node (ref "R11") (pin "1") (pinfunction "1_1") (pintype "passive"))
      (node (ref "R25") (pin "2") (pinfunction "2_2") (pintype "passive"))
      (node (ref "U$3") (pin "SDA") (pinfunction "SDA_SDA") (pintype "bidirectional"))
      (node (ref "U$4") (pin "3") (pinfunction "GPIO2_3") (pintype "bidirectional"))
      (node (ref "U$5") (pin "SDA") (pinfunction "SDA_SDA") (pintype "bidirectional"))
    )
    (net (code "48") (name "SDA_ADC") (class "Default")
      (node (ref "Q5") (pin "3") (pinfunction "D_3") (pintype "bidirectional"))
      (node (ref "R26") (pin "1") (pinfunction "1_1") (pintype "passive"))
      (node (ref "U2") (pin "6") (pinfunction "SDA_6") (pintype "bidirectional"))
    )
    (net (code "49") (name "TX") (class "Default")
      (node (ref "J9") (pin "3") (pinfunction "3_3") (pintype "passive"))
      (node (ref "U$4") (pin "8") (pinfunction "GPIO14_8") (pintype "bidirectional"))
    )
    (net (code "50") (name "unconnected-(U$3-PadAI2)") (class "Default")
      (node (ref "U$3") (pin "AI2") (pinfunction "AI2_AI2") (pintype "output"))
    )
    (net (code "51") (name "unconnected-(U$3-PadGI2)") (class "Default")
      (node (ref "U$3") (pin "GI2") (pinfunction "GI2_GI2") (pintype "output"))
    )
    (net (code "52") (name "unconnected-(U$4-3V3-Pad1)") (class "Default")
      (node (ref "U$4") (pin "1") (pinfunction "3V3_1") (pintype "bidirectional"))
    )
    (net (code "53") (name "unconnected-(U$4-3V3-Pad17)") (class "Default")
      (node (ref "U$4") (pin "17") (pinfunction "3V3_17") (pintype "bidirectional"))
    )
    (net (code "54") (name "unconnected-(U$4-GPIO6-Pad31)") (class "Default")
      (node (ref "U$4") (pin "31") (pinfunction "GPIO6_31") (pintype "bidirectional"))
    )
    (net (code "55") (name "unconnected-(U$4-GPIO18-Pad12)") (class "Default")
      (node (ref "U$4") (pin "12") (pinfunction "GPIO18_12") (pintype "bidirectional"))
    )
    (net (code "56") (name "unconnected-(U$4-ID_SC*-Pad28)") (class "Default")
      (node (ref "U$4") (pin "28") (pinfunction "ID_SC*_28") (pintype "bidirectional"))
    )
    (net (code "57") (name "unconnected-(U$4-ID_SD*-Pad27)") (class "Default")
      (node (ref "U$4") (pin "27") (pinfunction "ID_SD*_27") (pintype "bidirectional"))
    )
    (net (code "58") (name "unconnected-(U$5-PadPS0)") (class "Default")
      (node (ref "U$5") (pin "PS0") (pinfunction "PS0_PS0") (pintype "input"))
    )
    (net (code "59") (name "unconnected-(U$5-PadPS1)") (class "Default")
      (node (ref "U$5") (pin "PS1") (pinfunction "PS1_PS1") (pintype "input"))
    )
    (net (code "60") (name "unconnected-(U$6-SPLIT-Pad7)") (class "Default")
      (node (ref "U$6") (pin "7") (pinfunction "SPLIT_7") (pintype "bidirectional"))
    )
    (net (code "61") (name "unconnected-(U$6-STAT-Pad12)") (class "Default")
      (node (ref "U$6") (pin "12") (pinfunction "STAT_12") (pintype "bidirectional"))
    )
    (net (code "62") (name "unconnected-(U$9-13-Pad2)") (class "Default")
      (node (ref "U$9") (pin "2") (pinfunction "13_2") (pintype "passive"))
    )
    (net (code "63") (name "unconnected-(U$9-15-Pad4)") (class "Default")
      (node (ref "U$9") (pin "4") (pinfunction "15_4") (pintype "passive"))
    )
    (net (code "64") (name "unconnected-(U2-AIN0-Pad1)") (class "Default")
      (node (ref "U2") (pin "1") (pinfunction "AIN0_1") (pintype "bidirectional"))
    )
    (net (code "65") (name "~{AMP_FAULT}") (class "Default")
      (node (ref "Q2") (pin "1") (pinfunction "G_1") (pintype "bidirectional"))
      (node (ref "R19") (pin "1") (pinfunction "1_1") (pintype "passive"))
      (node (ref "U$8") (pin "9") (pinfunction "~{FAULTB}_9") (pintype "bidirectional"))
    )
    (net (code "66") (name "~{AMP_RESET}") (class "Default")
      (node (ref "Q3") (pin "1") (pinfunction "G_1") (pintype "bidirectional"))
      (node (ref "R22") (pin "1") (pinfunction "1_1") (pintype "passive"))
      (node (ref "U$4") (pin "7") (pinfunction "GPIO4_7") (pintype "bidirectional"))
      (node (ref "U$7") (pin "1") (pinfunction "P$1_1") (pintype "bidirectional"))
    )
  )
)
